# RectifierBoard.net
KiCad netlist of a schematic drawn in EAGLE
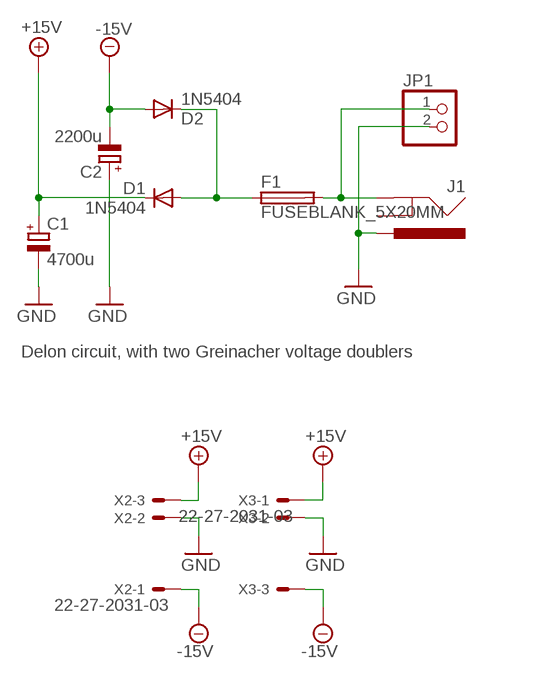
[diagram p0: schematic, sheet 1]

(export (version "E")
  (design (tool "Eeschema 10.0.6"))
  (components
    (comp (ref "C1")
      (value "4700u")
      (footprint "eagle-import:E7,5-18")
      (libsource (lib "eagle-import") (part "CPOL-EUE7.5-18"))
    )
    (comp (ref "C2")
      (value "2200u")
      (footprint "eagle-import:E7,5-18")
      (libsource (lib "eagle-import") (part "CPOL-EUE7.5-18"))
    )
    (comp (ref "D1")
      (value "1N5404")
      (footprint "eagle-import:DIODE-1N4001")
      (libsource (lib "eagle-import") (part "DIODE1N4001"))
    )
    (comp (ref "D2")
      (value "1N5404")
      (footprint "eagle-import:DIODE-1N4001")
      (libsource (lib "eagle-import") (part "DIODE1N4001"))
    )
    (comp (ref "F1")
      (value "FUSEBLANK_5X20MM")
      (footprint "eagle-import:FUSE_HOLDER_5X20MM")
      (libsource (lib "eagle-import") (part "FUSEBLANK_5X20MM"))
    )
    (comp (ref "J1")
      (value "POWER_JACKPTH")
      (footprint "eagle-import:POWER_JACK_PTH")
      (libsource (lib "eagle-import") (part "POWER_JACKPTH"))
    )
    (comp (ref "JP1")
      (value "PINHD-1X2")
      (footprint "eagle-import:1X02")
      (libsource (lib "eagle-import") (part "PINHD-1X2"))
    )
    (comp (ref "X2")
      (value "22-27-2031-03")
      (footprint "eagle-import:6410-03")
      (libsource (lib "eagle-import") (part "22-?-0327-2031"))
    )
    (comp (ref "X3")
      (value "22-27-2031-03")
      (footprint "eagle-import:6410-03")
      (libsource (lib "eagle-import") (part "22-?-0327-2031"))
    )
  )
  (nets
    (net (code "1") (name "+15V") (class "Default")
      (node (ref "C1") (pin "+") (pinfunction "+_+") (pintype "passive"))
      (node (ref "D1") (pin "C") (pinfunction "C_C") (pintype "passive"))
      (node (ref "X2") (pin "3") (pinfunction "S_3") (pintype "passive"))
      (node (ref "X3") (pin "1") (pinfunction "S_1") (pintype "passive"))
    )
    (net (code "2") (name "-15V") (class "Default")
      (node (ref "C2") (pin "-") (pinfunction "-_-") (pintype "passive"))
      (node (ref "D2") (pin "A") (pinfunction "A_A") (pintype "passive"))
      (node (ref "X2") (pin "1") (pinfunction "S_1") (pintype "passive"))
      (node (ref "X3") (pin "3") (pinfunction "S_3") (pintype "passive"))
    )
    (net (code "3") (name "GND") (class "Default")
      (node (ref "C1") (pin "-") (pinfunction "-_-") (pintype "passive"))
      (node (ref "C2") (pin "+") (pinfunction "+_+") (pintype "passive"))
      (node (ref "J1") (pin "PWR") (pinfunction "PWR_PWR") (pintype "bidirectional"))
      (node (ref "JP1") (pin "2") (pinfunction "2_2") (pintype "passive"))
      (node (ref "X2") (pin "2") (pinfunction "S_2") (pintype "passive"))
      (node (ref "X3") (pin "2") (pinfunction "S_2") (pintype "passive"))
    )
    (net (code "4") (name "Net-(D1-PadA)") (class "Default")
      (node (ref "D1") (pin "A") (pinfunction "A_A") (pintype "passive"))
      (node (ref "D2") (pin "C") (pinfunction "C_C") (pintype "passive"))
      (node (ref "F1") (pin "1") (pinfunction "1_1") (pintype "passive"))
    )
    (net (code "5") (name "Net-(F1-Pad2)") (class "Default")
      (node (ref "F1") (pin "2") (pinfunction "2_2") (pintype "passive"))
      (node (ref "J1") (pin "GND") (pinfunction "GND_GND") (pintype "bidirectional"))
      (node (ref "JP1") (pin "1") (pinfunction "1_1") (pintype "passive"))
    )
    (net (code "6") (name "unconnected-(J1-PadGNDBREAK)") (class "Default")
      (node (ref "J1") (pin "GNDBREAK") (pinfunction "GNDBREAK_GNDBREAK") (pintype "bidirectional"))
    )
  )
)
